# CAN_MAX3051.net
KiCad netlist of a schematic drawn in Altium Designer
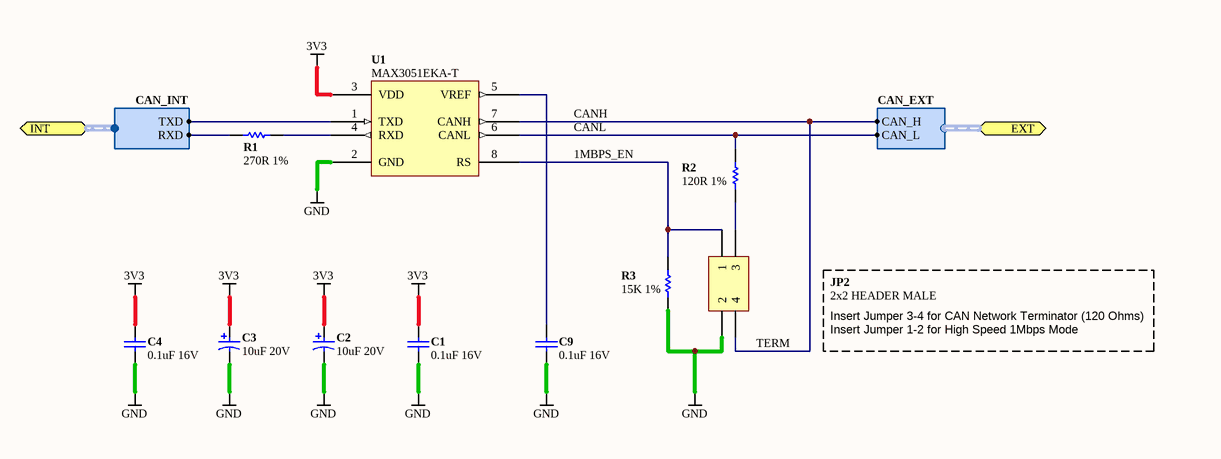
[diagram p0: CAN_MAX3051.SchDoc]

(export (version "E")
  (design (tool "Eeschema 10.0.6"))
  (components
    (comp (ref "C1")
      (value "0.1uF 16V")
      (footprint "CAPC1005-STAR")
      (description "Capacitor, Ceramic, 0.1uF 10% 16V 0402 (1005) X7R")
      (fields (field (name "TOLERANCE") "10 %"))
      (libsource (lib "altium-import") (part "root_0_CAP-NP_"))
    )
    (comp (ref "C2")
      (value "10uF 20V")
      (footprint "CAPC3528-STAR")
      (description "Capacitor, Tantalum, 10uF 10% 20V MCCT-B (3528)")
      (fields (field (name "TOLERANCE") "10 %"))
      (libsource (lib "altium-import") (part "root_0_CAP-P_"))
    )
    (comp (ref "C3")
      (value "10uF 20V")
      (footprint "CAPC3528-STAR")
      (description "Capacitor, Tantalum, 10uF 10% 20V MCCT-B (3528)")
      (fields (field (name "TOLERANCE") "10 %"))
      (libsource (lib "altium-import") (part "root_0_CAP-P_"))
    )
    (comp (ref "C4")
      (value "0.1uF 16V")
      (footprint "CAPC1005-STAR")
      (description "Capacitor, Ceramic, 0.1uF 10% 16V 0402 (1005) X7R")
      (fields (field (name "TOLERANCE") "10 %"))
      (libsource (lib "altium-import") (part "root_0_CAP-NP_"))
    )
    (comp (ref "C9")
      (value "0.1uF 16V")
      (footprint "CAPC1005-STAR")
      (description "Capacitor, Ceramic, 0.1uF 10% 16V 0402 (1005) X7R")
      (fields (field (name "TOLERANCE") "10 %"))
      (libsource (lib "altium-import") (part "root_0_CAP-NP_"))
    )
    (comp (ref "JP2")
      (value "2x2 HEADER MALE")
      (footprint "HDR2X2")
      (description "Header IDC, 2 x 2 Pin Vertical 2.54mm Pitch (Non-Boxed, Male)")
      (libsource (lib "AltiumDesignLibrary") (part "CON-HDR-2x2-STR"))
    )
    (comp (ref "R1")
      (value "270R 1%")
      (footprint "RESC1005-STAR")
      (description "Resistor, 270R 1% 0402 (1005)")
      (fields (field (name "TOLERANCE") "1 %"))
      (libsource (lib "altium-import") (part "root_1_RES_"))
    )
    (comp (ref "R2")
      (value "120R 1%")
      (footprint "RESC1005-STAR")
      (description "Resistor, 120R 1% 0402 (1005)")
      (fields (field (name "TOLERANCE") "1 %"))
      (libsource (lib "altium-import") (part "root_2_RES_"))
    )
    (comp (ref "R3")
      (value "15K 1%")
      (footprint "RESC1005-STAR")
      (description "Resistor, 15K 1% 0402 (1005)")
      (fields (field (name "TOLERANCE") "1 %"))
      (libsource (lib "altium-import") (part "root_2_RES_"))
    )
    (comp (ref "U1")
      (value "MAX3051EKA-T")
      (footprint "SOT65P280-8")
      (description "MAX3051EKA-T High-Speed CAN Transceiver SOT23-8")
      (libsource (lib "altium-import") (part "root_0_MCP2551_"))
    )
  )
  (nets
    (net (code "3") (name "/1MBPS_EN") (class "Default")
      (node (ref "JP2") (pin "1") (pinfunction "1_1") (pintype "passive"))
      (node (ref "R3") (pin "2") (pinfunction "2_2") (pintype "passive"))
      (node (ref "U1") (pin "8") (pinfunction "RS_8") (pintype "passive"))
    )
    (net (code "4") (name "/CANH") (class "Default")
      (node (ref "JP2") (pin "4") (pinfunction "4_4") (pintype "passive"))
      (node (ref "U1") (pin "7") (pinfunction "CANH_7") (pintype "output"))
    )
    (net (code "5") (name "/CANL") (class "Default")
      (node (ref "R2") (pin "2") (pinfunction "2_2") (pintype "passive"))
      (node (ref "U1") (pin "6") (pinfunction "CANL_6") (pintype "output"))
    )
    (net (code "6") (name "/RXD") (class "Default")
      (node (ref "R1") (pin "1") (pinfunction "1_1") (pintype "passive"))
    )
    (net (code "7") (name "/TXD") (class "Default")
      (node (ref "U1") (pin "1") (pinfunction "TXD_1") (pintype "input"))
    )
    (net (code "10") (name "3V3") (class "Default")
      (node (ref "C1") (pin "1") (pinfunction "1_1") (pintype "passive"))
      (node (ref "C2") (pin "1") (pinfunction "1_1") (pintype "passive"))
      (node (ref "C3") (pin "1") (pinfunction "1_1") (pintype "passive"))
      (node (ref "C4") (pin "1") (pinfunction "1_1") (pintype "passive"))
      (node (ref "U1") (pin "3") (pinfunction "VDD_3") (pintype "power_in"))
    )
    (net (code "11") (name "GND") (class "Default")
      (node (ref "C1") (pin "2") (pinfunction "2_2") (pintype "passive"))
      (node (ref "C2") (pin "2") (pinfunction "2_2") (pintype "passive"))
      (node (ref "C3") (pin "2") (pinfunction "2_2") (pintype "passive"))
      (node (ref "C4") (pin "2") (pinfunction "2_2") (pintype "passive"))
      (node (ref "C9") (pin "2") (pinfunction "2_2") (pintype "passive"))
      (node (ref "JP2") (pin "2") (pinfunction "2_2") (pintype "passive"))
      (node (ref "R3") (pin "1") (pinfunction "1_1") (pintype "passive"))
      (node (ref "U1") (pin "2") (pinfunction "GND_2") (pintype "power_in"))
    )
    (net (code "12") (name "Net-(JP2-Pad3)") (class "Default")
      (node (ref "JP2") (pin "3") (pinfunction "3_3") (pintype "passive"))
      (node (ref "R2") (pin "1") (pinfunction "1_1") (pintype "passive"))
    )
    (net (code "13") (name "Net-(U1-RXD)") (class "Default")
      (node (ref "R1") (pin "2") (pinfunction "2_2") (pintype "passive"))
      (node (ref "U1") (pin "4") (pinfunction "RXD_4") (pintype "output"))
    )
    (net (code "14") (name "Net-(U1-VREF)") (class "Default")
      (node (ref "C9") (pin "1") (pinfunction "1_1") (pintype "passive"))
      (node (ref "U1") (pin "5") (pinfunction "VREF_5") (pintype "output"))
    )
  )
)
